# IDCI_WifiNode_PER.net
KiCad netlist of a schematic drawn in Altium Designer
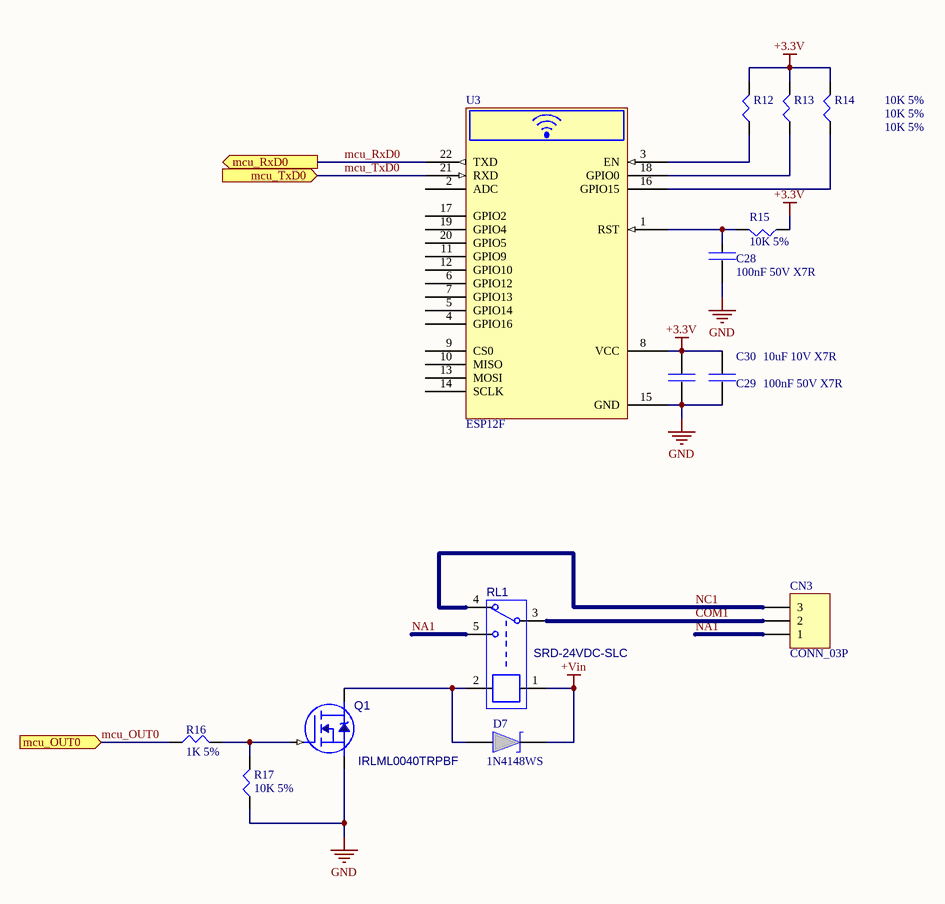
[diagram p0: IDCI_WifiNode_PER.SchDoc]

(export (version "E")
  (design (tool "Eeschema 10.0.6"))
  (components
    (comp (ref "C28")
      (value "100nF 50V X7R")
      (footprint "C_0805")
      (description "100nF x 50v")
      (libsource (lib "IDCI_WifiNode_2_R00") (part "Capacitor"))
    )
    (comp (ref "C29")
      (value "100nF 50V X7R")
      (footprint "C_0805")
      (description "100nF x 50v")
      (libsource (lib "IDCI_WifiNode_2_R00") (part "Capacitor"))
    )
    (comp (ref "C30")
      (value "10uF 10V X7R")
      (footprint "C_0805")
      (description "100nF x 50v")
      (libsource (lib "IDCI_WifiNode_2_R00") (part "Capacitor"))
    )
    (comp (ref "CN3")
      (value "CONN_03P")
      (footprint "TERMINAL_BLOCK_3_POLES")
      (description "Connector Generic 3 Vias")
      (libsource (lib "IDCI_WifiNode_2_R00") (part "CONN_03P"))
    )
    (comp (ref "D7")
      (value "1N4148WS")
      (footprint "Diode_SOD-323")
      (libsource (lib "IDCI_WifiNode_2_R00") (part "TVS_DIODE"))
    )
    (comp (ref "Q1")
      (value "IRLML0040TRPBF")
      (footprint "IC_SOT-23")
      (description "Mosfet N-Ch")
      (libsource (lib "IDCI_WifiNode_2_R00") (part "N_MOSFET_SOT23"))
    )
    (comp (ref "R12")
      (value "10K 5%")
      (footprint "R_0805")
      (libsource (lib "IDCI_WifiNode_2_R00") (part "Resistor"))
    )
    (comp (ref "R13")
      (value "10K 5%")
      (footprint "R_0805")
      (libsource (lib "IDCI_WifiNode_2_R00") (part "Resistor"))
    )
    (comp (ref "R14")
      (value "10K 5%")
      (footprint "R_0805")
      (libsource (lib "IDCI_WifiNode_2_R00") (part "Resistor"))
    )
    (comp (ref "R15")
      (value "10K 5%")
      (footprint "R_0805")
      (libsource (lib "IDCI_WifiNode_2_R00") (part "Resistor"))
    )
    (comp (ref "R16")
      (value "1K 5%")
      (footprint "R_0805")
      (libsource (lib "IDCI_WifiNode_2_R00") (part "Resistor"))
    )
    (comp (ref "R17")
      (value "10K 5%")
      (footprint "R_0805")
      (libsource (lib "IDCI_WifiNode_2_R00") (part "Resistor"))
    )
    (comp (ref "RL1")
      (value "SRD-24VDC-SLC")
      (footprint "RELAY")
      (description "Relay SPDT")
      (libsource (lib "IDCI_WifiNode_2_R00") (part "RELAY SPDT"))
    )
    (comp (ref "U3")
      (value "ESP12F")
      (footprint "ESP12F")
      (description "Wifi Module")
      (libsource (lib "IDCI_WifiNode_2_R00") (part "ESP12F Wifi Module"))
    )
  )
  (nets
    (net (code "1") (name "+3.3V") (class "Default")
      (node (ref "C29") (pin "2") (pinfunction "2_2") (pintype "passive"))
      (node (ref "C30") (pin "2") (pinfunction "2_2") (pintype "passive"))
      (node (ref "R12") (pin "2") (pinfunction "2_2") (pintype "passive"))
      (node (ref "R13") (pin "2") (pinfunction "2_2") (pintype "passive"))
      (node (ref "R14") (pin "2") (pinfunction "2_2") (pintype "passive"))
      (node (ref "R15") (pin "1") (pinfunction "1_1") (pintype "passive"))
      (node (ref "U3") (pin "8") (pinfunction "VCC_8") (pintype "power_in"))
    )
    (net (code "2") (name "+Vin") (class "Default")
      (node (ref "D7") (pin "2") (pinfunction "2_2") (pintype "passive"))
      (node (ref "RL1") (pin "1") (pinfunction "1_1") (pintype "passive"))
    )
    (net (code "3") (name "/COM1") (class "Default")
      (node (ref "CN3") (pin "2") (pinfunction "2_2") (pintype "passive"))
      (node (ref "RL1") (pin "3") (pinfunction "3_3") (pintype "passive"))
    )
    (net (code "4") (name "/NA1") (class "Default")
      (node (ref "CN3") (pin "1") (pinfunction "1_1") (pintype "passive"))
      (node (ref "RL1") (pin "5") (pinfunction "5_5") (pintype "passive"))
    )
    (net (code "5") (name "/NC1") (class "Default")
      (node (ref "CN3") (pin "3") (pinfunction "3_3") (pintype "passive"))
      (node (ref "RL1") (pin "4") (pinfunction "4_4") (pintype "passive"))
    )
    (net (code "6") (name "/mcu_OUT0") (class "Default")
      (node (ref "R16") (pin "1") (pinfunction "1_1") (pintype "passive"))
    )
    (net (code "7") (name "/mcu_RxD0") (class "Default")
      (node (ref "U3") (pin "22") (pinfunction "TXD_22") (pintype "output"))
    )
    (net (code "8") (name "/mcu_TxD0") (class "Default")
      (node (ref "U3") (pin "21") (pinfunction "RXD_21") (pintype "input"))
    )
    (net (code "9") (name "GND") (class "Default")
      (node (ref "C28") (pin "1") (pinfunction "1_1") (pintype "passive"))
      (node (ref "C29") (pin "1") (pinfunction "1_1") (pintype "passive"))
      (node (ref "C30") (pin "1") (pinfunction "1_1") (pintype "passive"))
      (node (ref "Q1") (pin "2") (pinfunction "SOURCE_2") (pintype "passive"))
      (node (ref "R17") (pin "1") (pinfunction "1_1") (pintype "passive"))
      (node (ref "U3") (pin "15") (pinfunction "GND_15") (pintype "power_in"))
    )
    (net (code "10") (name "Net-(Q1-DRAIN)") (class "Default")
      (node (ref "D7") (pin "1") (pinfunction "1_1") (pintype "passive"))
      (node (ref "Q1") (pin "3") (pinfunction "DRAIN_3") (pintype "passive"))
      (node (ref "RL1") (pin "2") (pinfunction "2_2") (pintype "passive"))
    )
    (net (code "11") (name "Net-(Q1-GATE)") (class "Default")
      (node (ref "Q1") (pin "1") (pinfunction "GATE_1") (pintype "input"))
      (node (ref "R16") (pin "2") (pinfunction "2_2") (pintype "passive"))
      (node (ref "R17") (pin "2") (pinfunction "2_2") (pintype "passive"))
    )
    (net (code "12") (name "Net-(U3-EN)") (class "Default")
      (node (ref "R12") (pin "1") (pinfunction "1_1") (pintype "passive"))
      (node (ref "U3") (pin "3") (pinfunction "EN_3") (pintype "input"))
    )
    (net (code "13") (name "Net-(U3-GPIO0)") (class "Default")
      (node (ref "R13") (pin "1") (pinfunction "1_1") (pintype "passive"))
      (node (ref "U3") (pin "18") (pinfunction "GPIO0_18") (pintype "passive"))
    )
    (net (code "14") (name "Net-(U3-GPIO15)") (class "Default")
      (node (ref "R14") (pin "1") (pinfunction "1_1") (pintype "passive"))
      (node (ref "U3") (pin "16") (pinfunction "GPIO15_16") (pintype "passive"))
    )
    (net (code "15") (name "Net-(U3-RST)") (class "Default")
      (node (ref "C28") (pin "2") (pinfunction "2_2") (pintype "passive"))
      (node (ref "R15") (pin "2") (pinfunction "2_2") (pintype "passive"))
      (node (ref "U3") (pin "1") (pinfunction "RST_1") (pintype "input"))
    )
    (net (code "16") (name "unconnected-(U3-ADC-Pad2)") (class "Default")
      (node (ref "U3") (pin "2") (pinfunction "ADC_2") (pintype "passive"))
    )
    (net (code "17") (name "unconnected-(U3-CS0-Pad9)") (class "Default")
      (node (ref "U3") (pin "9") (pinfunction "CS0_9") (pintype "passive"))
    )
    (net (code "18") (name "unconnected-(U3-GPIO2-Pad17)") (class "Default")
      (node (ref "U3") (pin "17") (pinfunction "GPIO2_17") (pintype "passive"))
    )
    (net (code "19") (name "unconnected-(U3-GPIO4-Pad19)") (class "Default")
      (node (ref "U3") (pin "19") (pinfunction "GPIO4_19") (pintype "passive"))
    )
    (net (code "20") (name "unconnected-(U3-GPIO5-Pad20)") (class "Default")
      (node (ref "U3") (pin "20") (pinfunction "GPIO5_20") (pintype "passive"))
    )
    (net (code "21") (name "unconnected-(U3-GPIO9-Pad11)") (class "Default")
      (node (ref "U3") (pin "11") (pinfunction "GPIO9_11") (pintype "passive"))
    )
    (net (code "22") (name "unconnected-(U3-GPIO10-Pad12)") (class "Default")
      (node (ref "U3") (pin "12") (pinfunction "GPIO10_12") (pintype "passive"))
    )
    (net (code "23") (name "unconnected-(U3-GPIO12-Pad6)") (class "Default")
      (node (ref "U3") (pin "6") (pinfunction "GPIO12_6") (pintype "passive"))
    )
    (net (code "24") (name "unconnected-(U3-GPIO13-Pad7)") (class "Default")
      (node (ref "U3") (pin "7") (pinfunction "GPIO13_7") (pintype "passive"))
    )
    (net (code "25") (name "unconnected-(U3-GPIO14-Pad5)") (class "Default")
      (node (ref "U3") (pin "5") (pinfunction "GPIO14_5") (pintype "passive"))
    )
    (net (code "26") (name "unconnected-(U3-GPIO16-Pad4)") (class "Default")
      (node (ref "U3") (pin "4") (pinfunction "GPIO16_4") (pintype "passive"))
    )
    (net (code "27") (name "unconnected-(U3-MISO-Pad10)") (class "Default")
      (node (ref "U3") (pin "10") (pinfunction "MISO_10") (pintype "passive"))
    )
    (net (code "28") (name "unconnected-(U3-MOSI-Pad13)") (class "Default")
      (node (ref "U3") (pin "13") (pinfunction "MOSI_13") (pintype "passive"))
    )
    (net (code "29") (name "unconnected-(U3-SCLK-Pad14)") (class "Default")
      (node (ref "U3") (pin "14") (pinfunction "SCLK_14") (pintype "passive"))
    )
  )
)
